# Arturo_Verasv22.net
KiCad netlist of a schematic drawn in EAGLE
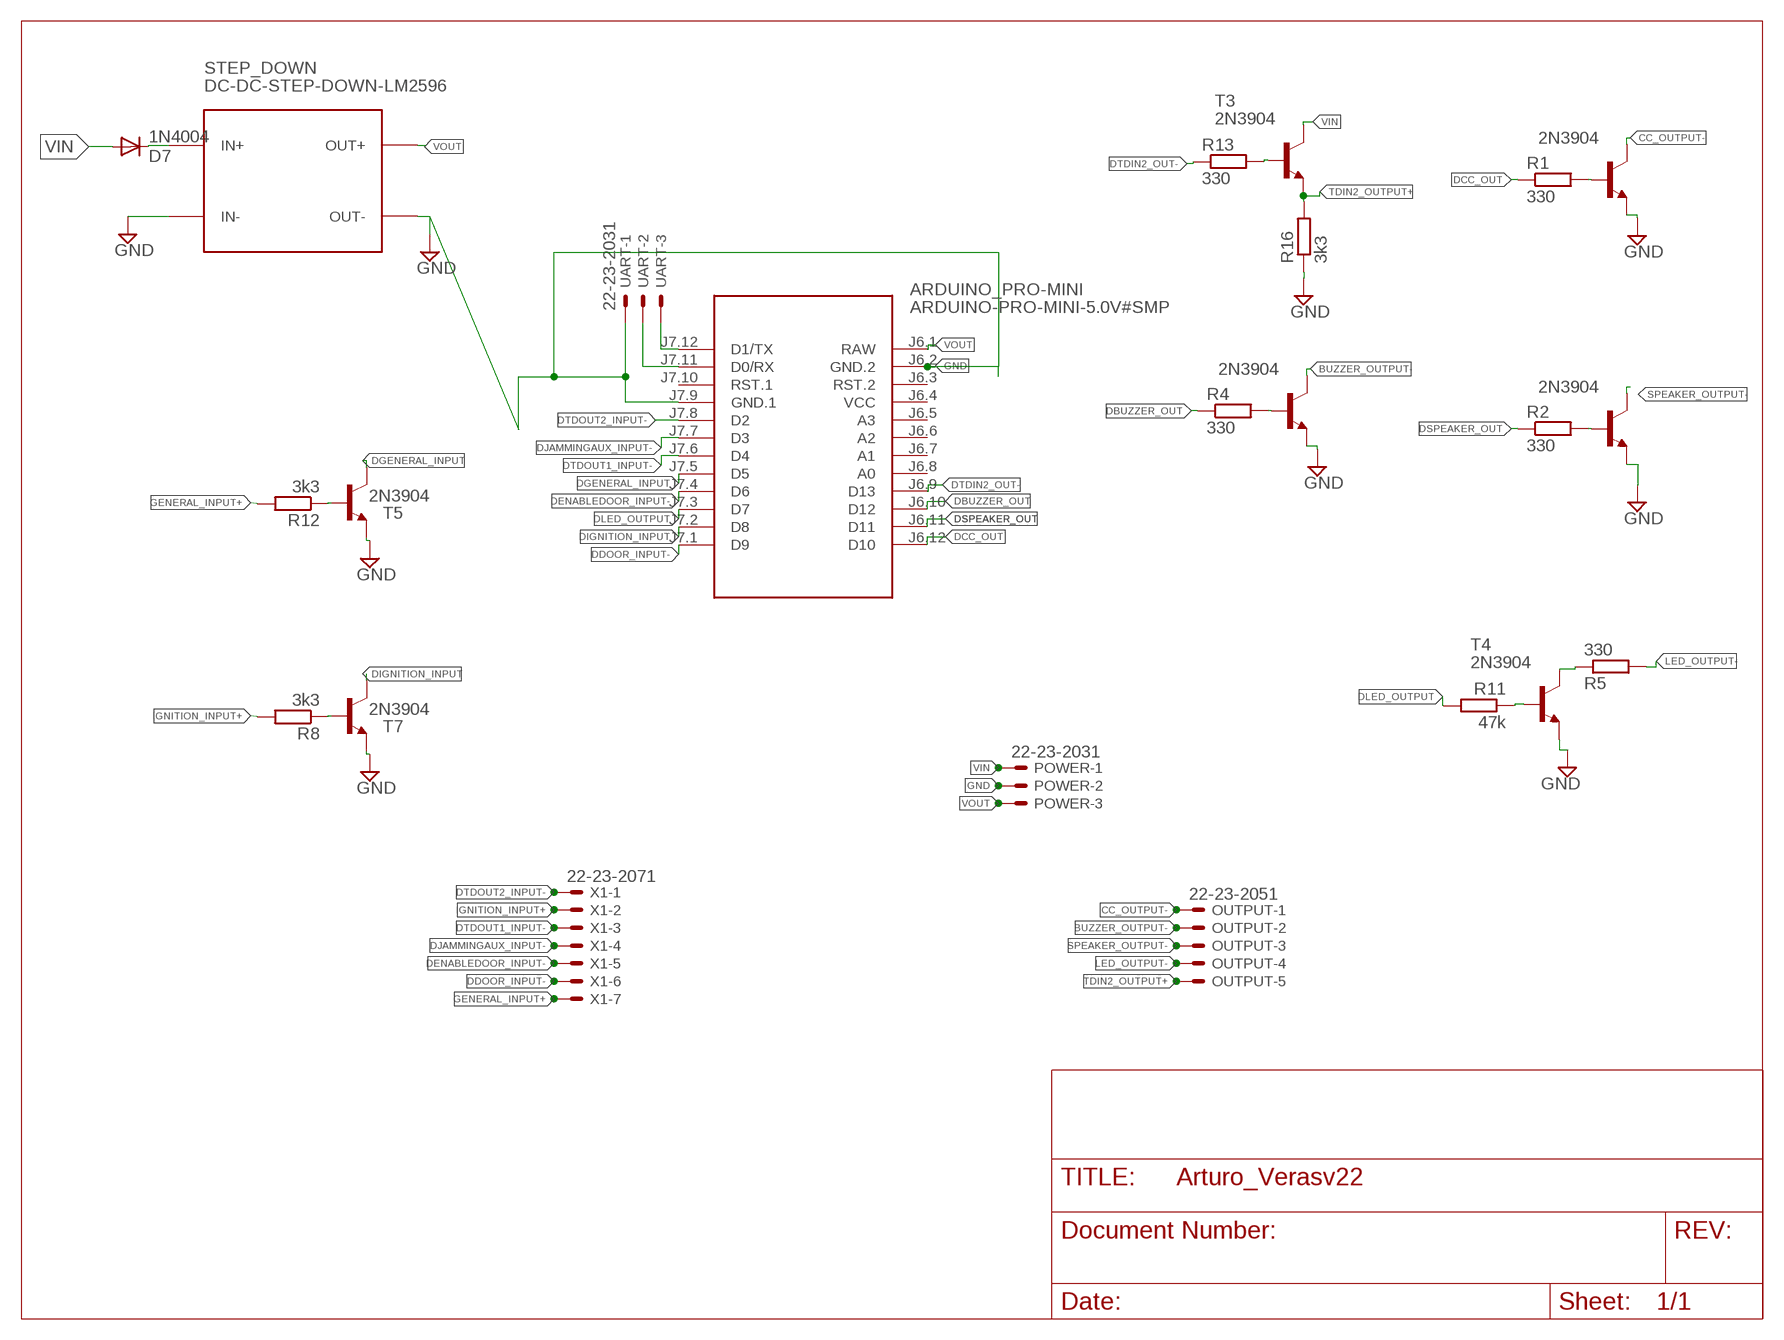
[diagram p0: schematic, sheet 1]

(export (version "E")
  (design (tool "Eeschema 10.0.6"))
  (components
    (comp (ref "ARDUINO_PRO-MINI")
      (value "ARDUINO-PRO-MINI-5.0V#SMP")
      (footprint "eagle-import:ARDUINO-PRO-MINI#SMP")
      (libsource (lib "eagle-import") (part "ARDUINO-PRO-MINI-#SMP5.0V"))
    )
    (comp (ref "D7")
      (value "1N4004")
      (footprint "eagle-import:DO41-10")
      (libsource (lib "eagle-import") (part "1N4004"))
    )
    (comp (ref "OUTPUT")
      (value "22-23-2051")
      (footprint "eagle-import:22-23-2051")
      (fields (field (name "MF") "MOLEX"))
      (libsource (lib "eagle-import") (part "22-23-2051"))
    )
    (comp (ref "POWER")
      (value "22-23-2031")
      (footprint "eagle-import:22-23-2031")
      (fields (field (name "MF") "MOLEX"))
      (libsource (lib "eagle-import") (part "22-23-2031"))
    )
    (comp (ref "R1")
      (value "330")
      (footprint "eagle-import:0204_7")
      (libsource (lib "eagle-import") (part "R-EU_0204/7"))
    )
    (comp (ref "R2")
      (value "330")
      (footprint "eagle-import:0204_7")
      (libsource (lib "eagle-import") (part "R-EU_0204/7"))
    )
    (comp (ref "R4")
      (value "330")
      (footprint "eagle-import:0204_7")
      (libsource (lib "eagle-import") (part "R-EU_0204/7"))
    )
    (comp (ref "R5")
      (value "330")
      (footprint "eagle-import:0204_7")
      (libsource (lib "eagle-import") (part "R-EU_0204/7"))
    )
    (comp (ref "R8")
      (value "3k3")
      (footprint "eagle-import:0204_7")
      (libsource (lib "eagle-import") (part "R-EU_0204/7"))
    )
    (comp (ref "R11")
      (value "47k")
      (footprint "eagle-import:0204_7")
      (libsource (lib "eagle-import") (part "R-EU_0204/7"))
    )
    (comp (ref "R12")
      (value "3k3")
      (footprint "eagle-import:0204_7")
      (libsource (lib "eagle-import") (part "R-EU_0204/7"))
    )
    (comp (ref "R13")
      (value "330")
      (footprint "eagle-import:0204_7")
      (libsource (lib "eagle-import") (part "R-EU_0204/7"))
    )
    (comp (ref "R16")
      (value "3k3")
      (footprint "eagle-import:0204_7")
      (libsource (lib "eagle-import") (part "R-EU_0204/7"))
    )
    (comp (ref "STEP_DOWN")
      (value "DC-DC-STEP-DOWN-LM2596")
      (footprint "eagle-import:DC-DC-STEP-DOWN-LM2596")
      (libsource (lib "eagle-import") (part "DC-DC-STEP-DOWN-LM2596"))
    )
    (comp (ref "T1")
      (value "2N3904")
      (footprint "eagle-import:TO92")
      (libsource (lib "eagle-import") (part "2N3904"))
    )
    (comp (ref "T3")
      (value "2N3904")
      (footprint "eagle-import:TO92")
      (libsource (lib "eagle-import") (part "2N3904"))
    )
    (comp (ref "T4")
      (value "2N3904")
      (footprint "eagle-import:TO92")
      (libsource (lib "eagle-import") (part "2N3904"))
    )
    (comp (ref "T5")
      (value "2N3904")
      (footprint "eagle-import:TO92")
      (libsource (lib "eagle-import") (part "2N3904"))
    )
    (comp (ref "T6")
      (value "2N3904")
      (footprint "eagle-import:TO92")
      (libsource (lib "eagle-import") (part "2N3904"))
    )
    (comp (ref "T7")
      (value "2N3904")
      (footprint "eagle-import:TO92")
      (libsource (lib "eagle-import") (part "2N3904"))
    )
    (comp (ref "T8")
      (value "2N3904")
      (footprint "eagle-import:TO92")
      (libsource (lib "eagle-import") (part "2N3904"))
    )
    (comp (ref "UART")
      (value "22-23-2031")
      (footprint "eagle-import:22-23-2031")
      (fields (field (name "MF") "MOLEX"))
      (libsource (lib "eagle-import") (part "22-23-2031"))
    )
    (comp (ref "X1")
      (value "22-23-2071")
      (footprint "eagle-import:22-23-2071")
      (fields (field (name "MF") "MOLEX"))
      (libsource (lib "eagle-import") (part "22-23-2071"))
    )
  )
  (nets
    (net (code "1") (name "/VCC") (class "Default")
      (node (ref "ARDUINO_PRO-MINI") (pin "J6.4") (pinfunction "VCC_J6.4") (pintype "power_in"))
    )
    (net (code "2") (name "BUZZER_OUTPUT-") (class "Default")
      (node (ref "OUTPUT") (pin "2") (pinfunction "S_2") (pintype "passive"))
      (node (ref "T6") (pin "1") (pinfunction "C_1") (pintype "passive"))
    )
    (net (code "3") (name "CC_OUTPUT-") (class "Default")
      (node (ref "OUTPUT") (pin "1") (pinfunction "S_1") (pintype "passive"))
      (node (ref "T8") (pin "1") (pinfunction "C_1") (pintype "passive"))
    )
    (net (code "4") (name "DBUZZER_OUT") (class "Default")
      (node (ref "ARDUINO_PRO-MINI") (pin "J6.10") (pinfunction "D12_J6.10") (pintype "bidirectional"))
      (node (ref "R4") (pin "1") (pinfunction "1_1") (pintype "passive"))
    )
    (net (code "5") (name "DCC_OUT") (class "Default")
      (node (ref "ARDUINO_PRO-MINI") (pin "J6.12") (pinfunction "D10_J6.12") (pintype "bidirectional"))
      (node (ref "R1") (pin "1") (pinfunction "1_1") (pintype "passive"))
    )
    (net (code "6") (name "DDOOR_INPUT-") (class "Default")
      (node (ref "ARDUINO_PRO-MINI") (pin "J7.1") (pinfunction "D9_J7.1") (pintype "bidirectional"))
      (node (ref "X1") (pin "6") (pinfunction "S_6") (pintype "passive"))
    )
    (net (code "7") (name "DENABLEDOOR_INPUT-") (class "Default")
      (node (ref "ARDUINO_PRO-MINI") (pin "J7.4") (pinfunction "D6_J7.4") (pintype "bidirectional"))
      (node (ref "X1") (pin "5") (pinfunction "S_5") (pintype "passive"))
    )
    (net (code "8") (name "DGENERAL_INPUT") (class "Default")
      (node (ref "ARDUINO_PRO-MINI") (pin "J7.5") (pinfunction "D5_J7.5") (pintype "bidirectional"))
      (node (ref "T5") (pin "1") (pinfunction "C_1") (pintype "passive"))
    )
    (net (code "9") (name "DIGNITION_INPUT") (class "Default")
      (node (ref "ARDUINO_PRO-MINI") (pin "J7.2") (pinfunction "D8_J7.2") (pintype "bidirectional"))
      (node (ref "T7") (pin "1") (pinfunction "C_1") (pintype "passive"))
    )
    (net (code "10") (name "DJAMMINGAUX_INPUT-") (class "Default")
      (node (ref "ARDUINO_PRO-MINI") (pin "J7.7") (pinfunction "D3_J7.7") (pintype "bidirectional"))
      (node (ref "X1") (pin "4") (pinfunction "S_4") (pintype "passive"))
    )
    (net (code "11") (name "DLED_OUTPUT") (class "Default")
      (node (ref "ARDUINO_PRO-MINI") (pin "J7.3") (pinfunction "D7_J7.3") (pintype "bidirectional"))
      (node (ref "R11") (pin "2") (pinfunction "2_2") (pintype "passive"))
    )
    (net (code "12") (name "DSPEAKER_OUT") (class "Default")
      (node (ref "ARDUINO_PRO-MINI") (pin "J6.11") (pinfunction "D11_J6.11") (pintype "bidirectional"))
      (node (ref "R2") (pin "1") (pinfunction "1_1") (pintype "passive"))
    )
    (net (code "13") (name "DTDIN2_OUT-") (class "Default")
      (node (ref "ARDUINO_PRO-MINI") (pin "J6.9") (pinfunction "D13_J6.9") (pintype "bidirectional"))
      (node (ref "R13") (pin "1") (pinfunction "1_1") (pintype "passive"))
    )
    (net (code "14") (name "DTDOUT1_INPUT-") (class "Default")
      (node (ref "ARDUINO_PRO-MINI") (pin "J7.6") (pinfunction "D4_J7.6") (pintype "bidirectional"))
      (node (ref "X1") (pin "3") (pinfunction "S_3") (pintype "passive"))
    )
    (net (code "15") (name "DTDOUT2_INPUT-") (class "Default")
      (node (ref "ARDUINO_PRO-MINI") (pin "J7.8") (pinfunction "D2_J7.8") (pintype "bidirectional"))
      (node (ref "X1") (pin "1") (pinfunction "S_1") (pintype "passive"))
    )
    (net (code "16") (name "GENERAL_INPUT+") (class "Default")
      (node (ref "R12") (pin "2") (pinfunction "2_2") (pintype "passive"))
      (node (ref "X1") (pin "7") (pinfunction "S_7") (pintype "passive"))
    )
    (net (code "17") (name "GND") (class "Default")
      (node (ref "ARDUINO_PRO-MINI") (pin "J6.2") (pinfunction "GND.2_J6.2") (pintype "power_in"))
      (node (ref "ARDUINO_PRO-MINI") (pin "J7.9") (pinfunction "GND.1_J7.9") (pintype "power_in"))
      (node (ref "POWER") (pin "2") (pinfunction "S_2") (pintype "passive"))
      (node (ref "R16") (pin "1") (pinfunction "1_1") (pintype "passive"))
      (node (ref "STEP_DOWN") (pin "IN-") (pinfunction "IN-_IN-") (pintype "bidirectional"))
      (node (ref "STEP_DOWN") (pin "OUT-") (pinfunction "OUT-_OUT-") (pintype "bidirectional"))
      (node (ref "T1") (pin "3") (pinfunction "E_3") (pintype "passive"))
      (node (ref "T4") (pin "3") (pinfunction "E_3") (pintype "passive"))
      (node (ref "T5") (pin "3") (pinfunction "E_3") (pintype "passive"))
      (node (ref "T6") (pin "3") (pinfunction "E_3") (pintype "passive"))
      (node (ref "T7") (pin "3") (pinfunction "E_3") (pintype "passive"))
      (node (ref "T8") (pin "3") (pinfunction "E_3") (pintype "passive"))
      (node (ref "UART") (pin "1") (pinfunction "S_1") (pintype "passive"))
    )
    (net (code "18") (name "IGNITION_INPUT+") (class "Default")
      (node (ref "R8") (pin "2") (pinfunction "2_2") (pintype "passive"))
      (node (ref "X1") (pin "2") (pinfunction "S_2") (pintype "passive"))
    )
    (net (code "19") (name "LED_OUTPUT-") (class "Default")
      (node (ref "OUTPUT") (pin "4") (pinfunction "S_4") (pintype "passive"))
      (node (ref "R5") (pin "2") (pinfunction "2_2") (pintype "passive"))
    )
    (net (code "20") (name "Net-(ARDUINO_PRO-MINI-D0{slash}RX)") (class "Default")
      (node (ref "ARDUINO_PRO-MINI") (pin "J7.11") (pinfunction "D0/RX_J7.11") (pintype "bidirectional"))
      (node (ref "UART") (pin "2") (pinfunction "S_2") (pintype "passive"))
    )
    (net (code "21") (name "Net-(ARDUINO_PRO-MINI-D1{slash}TX)") (class "Default")
      (node (ref "ARDUINO_PRO-MINI") (pin "J7.12") (pinfunction "D1/TX_J7.12") (pintype "bidirectional"))
      (node (ref "UART") (pin "3") (pinfunction "S_3") (pintype "passive"))
    )
    (net (code "22") (name "Net-(D7-PadC)") (class "Default")
      (node (ref "D7") (pin "C") (pinfunction "C_C") (pintype "passive"))
      (node (ref "STEP_DOWN") (pin "IN+") (pinfunction "IN+_IN+") (pintype "bidirectional"))
    )
    (net (code "23") (name "Net-(T1-B)") (class "Default")
      (node (ref "R2") (pin "2") (pinfunction "2_2") (pintype "passive"))
      (node (ref "T1") (pin "2") (pinfunction "B_2") (pintype "passive"))
    )
    (net (code "24") (name "Net-(T3-B)") (class "Default")
      (node (ref "R13") (pin "2") (pinfunction "2_2") (pintype "passive"))
      (node (ref "T3") (pin "2") (pinfunction "B_2") (pintype "passive"))
    )
    (net (code "25") (name "Net-(T4-B)") (class "Default")
      (node (ref "R11") (pin "1") (pinfunction "1_1") (pintype "passive"))
      (node (ref "T4") (pin "2") (pinfunction "B_2") (pintype "passive"))
    )
    (net (code "26") (name "Net-(T4-C)") (class "Default")
      (node (ref "R5") (pin "1") (pinfunction "1_1") (pintype "passive"))
      (node (ref "T4") (pin "1") (pinfunction "C_1") (pintype "passive"))
    )
    (net (code "27") (name "Net-(T5-B)") (class "Default")
      (node (ref "R12") (pin "1") (pinfunction "1_1") (pintype "passive"))
      (node (ref "T5") (pin "2") (pinfunction "B_2") (pintype "passive"))
    )
    (net (code "28") (name "Net-(T6-B)") (class "Default")
      (node (ref "R4") (pin "2") (pinfunction "2_2") (pintype "passive"))
      (node (ref "T6") (pin "2") (pinfunction "B_2") (pintype "passive"))
    )
    (net (code "29") (name "Net-(T7-B)") (class "Default")
      (node (ref "R8") (pin "1") (pinfunction "1_1") (pintype "passive"))
      (node (ref "T7") (pin "2") (pinfunction "B_2") (pintype "passive"))
    )
    (net (code "30") (name "Net-(T8-B)") (class "Default")
      (node (ref "R1") (pin "2") (pinfunction "2_2") (pintype "passive"))
      (node (ref "T8") (pin "2") (pinfunction "B_2") (pintype "passive"))
    )
    (net (code "31") (name "SPEAKER_OUTPUT-") (class "Default")
      (node (ref "OUTPUT") (pin "3") (pinfunction "S_3") (pintype "passive"))
      (node (ref "T1") (pin "1") (pinfunction "C_1") (pintype "passive"))
    )
    (net (code "32") (name "TDIN2_OUTPUT+") (class "Default")
      (node (ref "OUTPUT") (pin "5") (pinfunction "S_5") (pintype "passive"))
      (node (ref "R16") (pin "2") (pinfunction "2_2") (pintype "passive"))
      (node (ref "T3") (pin "3") (pinfunction "E_3") (pintype "passive"))
    )
    (net (code "33") (name "VIN") (class "Default")
      (node (ref "D7") (pin "A") (pinfunction "A_A") (pintype "passive"))
      (node (ref "POWER") (pin "1") (pinfunction "S_1") (pintype "passive"))
      (node (ref "T3") (pin "1") (pinfunction "C_1") (pintype "passive"))
    )
    (net (code "34") (name "VOUT") (class "Default")
      (node (ref "ARDUINO_PRO-MINI") (pin "J6.1") (pinfunction "RAW_J6.1") (pintype "power_in"))
      (node (ref "POWER") (pin "3") (pinfunction "S_3") (pintype "passive"))
      (node (ref "STEP_DOWN") (pin "OUT+") (pinfunction "OUT+_OUT+") (pintype "bidirectional"))
    )
    (net (code "35") (name "unconnected-(ARDUINO_PRO-MINI-A0-PadJ6.8)") (class "Default")
      (node (ref "ARDUINO_PRO-MINI") (pin "J6.8") (pinfunction "A0_J6.8") (pintype "bidirectional"))
    )
    (net (code "36") (name "unconnected-(ARDUINO_PRO-MINI-A1-PadJ6.7)") (class "Default")
      (node (ref "ARDUINO_PRO-MINI") (pin "J6.7") (pinfunction "A1_J6.7") (pintype "bidirectional"))
    )
    (net (code "37") (name "unconnected-(ARDUINO_PRO-MINI-A2-PadJ6.6)") (class "Default")
      (node (ref "ARDUINO_PRO-MINI") (pin "J6.6") (pinfunction "A2_J6.6") (pintype "bidirectional"))
    )
    (net (code "38") (name "unconnected-(ARDUINO_PRO-MINI-A3-PadJ6.5)") (class "Default")
      (node (ref "ARDUINO_PRO-MINI") (pin "J6.5") (pinfunction "A3_J6.5") (pintype "bidirectional"))
    )
    (net (code "39") (name "unconnected-(ARDUINO_PRO-MINI-RST.1-PadJ7.10)") (class "Default")
      (node (ref "ARDUINO_PRO-MINI") (pin "J7.10") (pinfunction "RST.1_J7.10") (pintype "bidirectional"))
    )
    (net (code "40") (name "unconnected-(ARDUINO_PRO-MINI-RST.2-PadJ6.3)") (class "Default")
      (node (ref "ARDUINO_PRO-MINI") (pin "J6.3") (pinfunction "RST.2_J6.3") (pintype "bidirectional"))
    )
  )
)
